# nuc5v2.net
KiCad netlist of a schematic drawn in Altium Designer
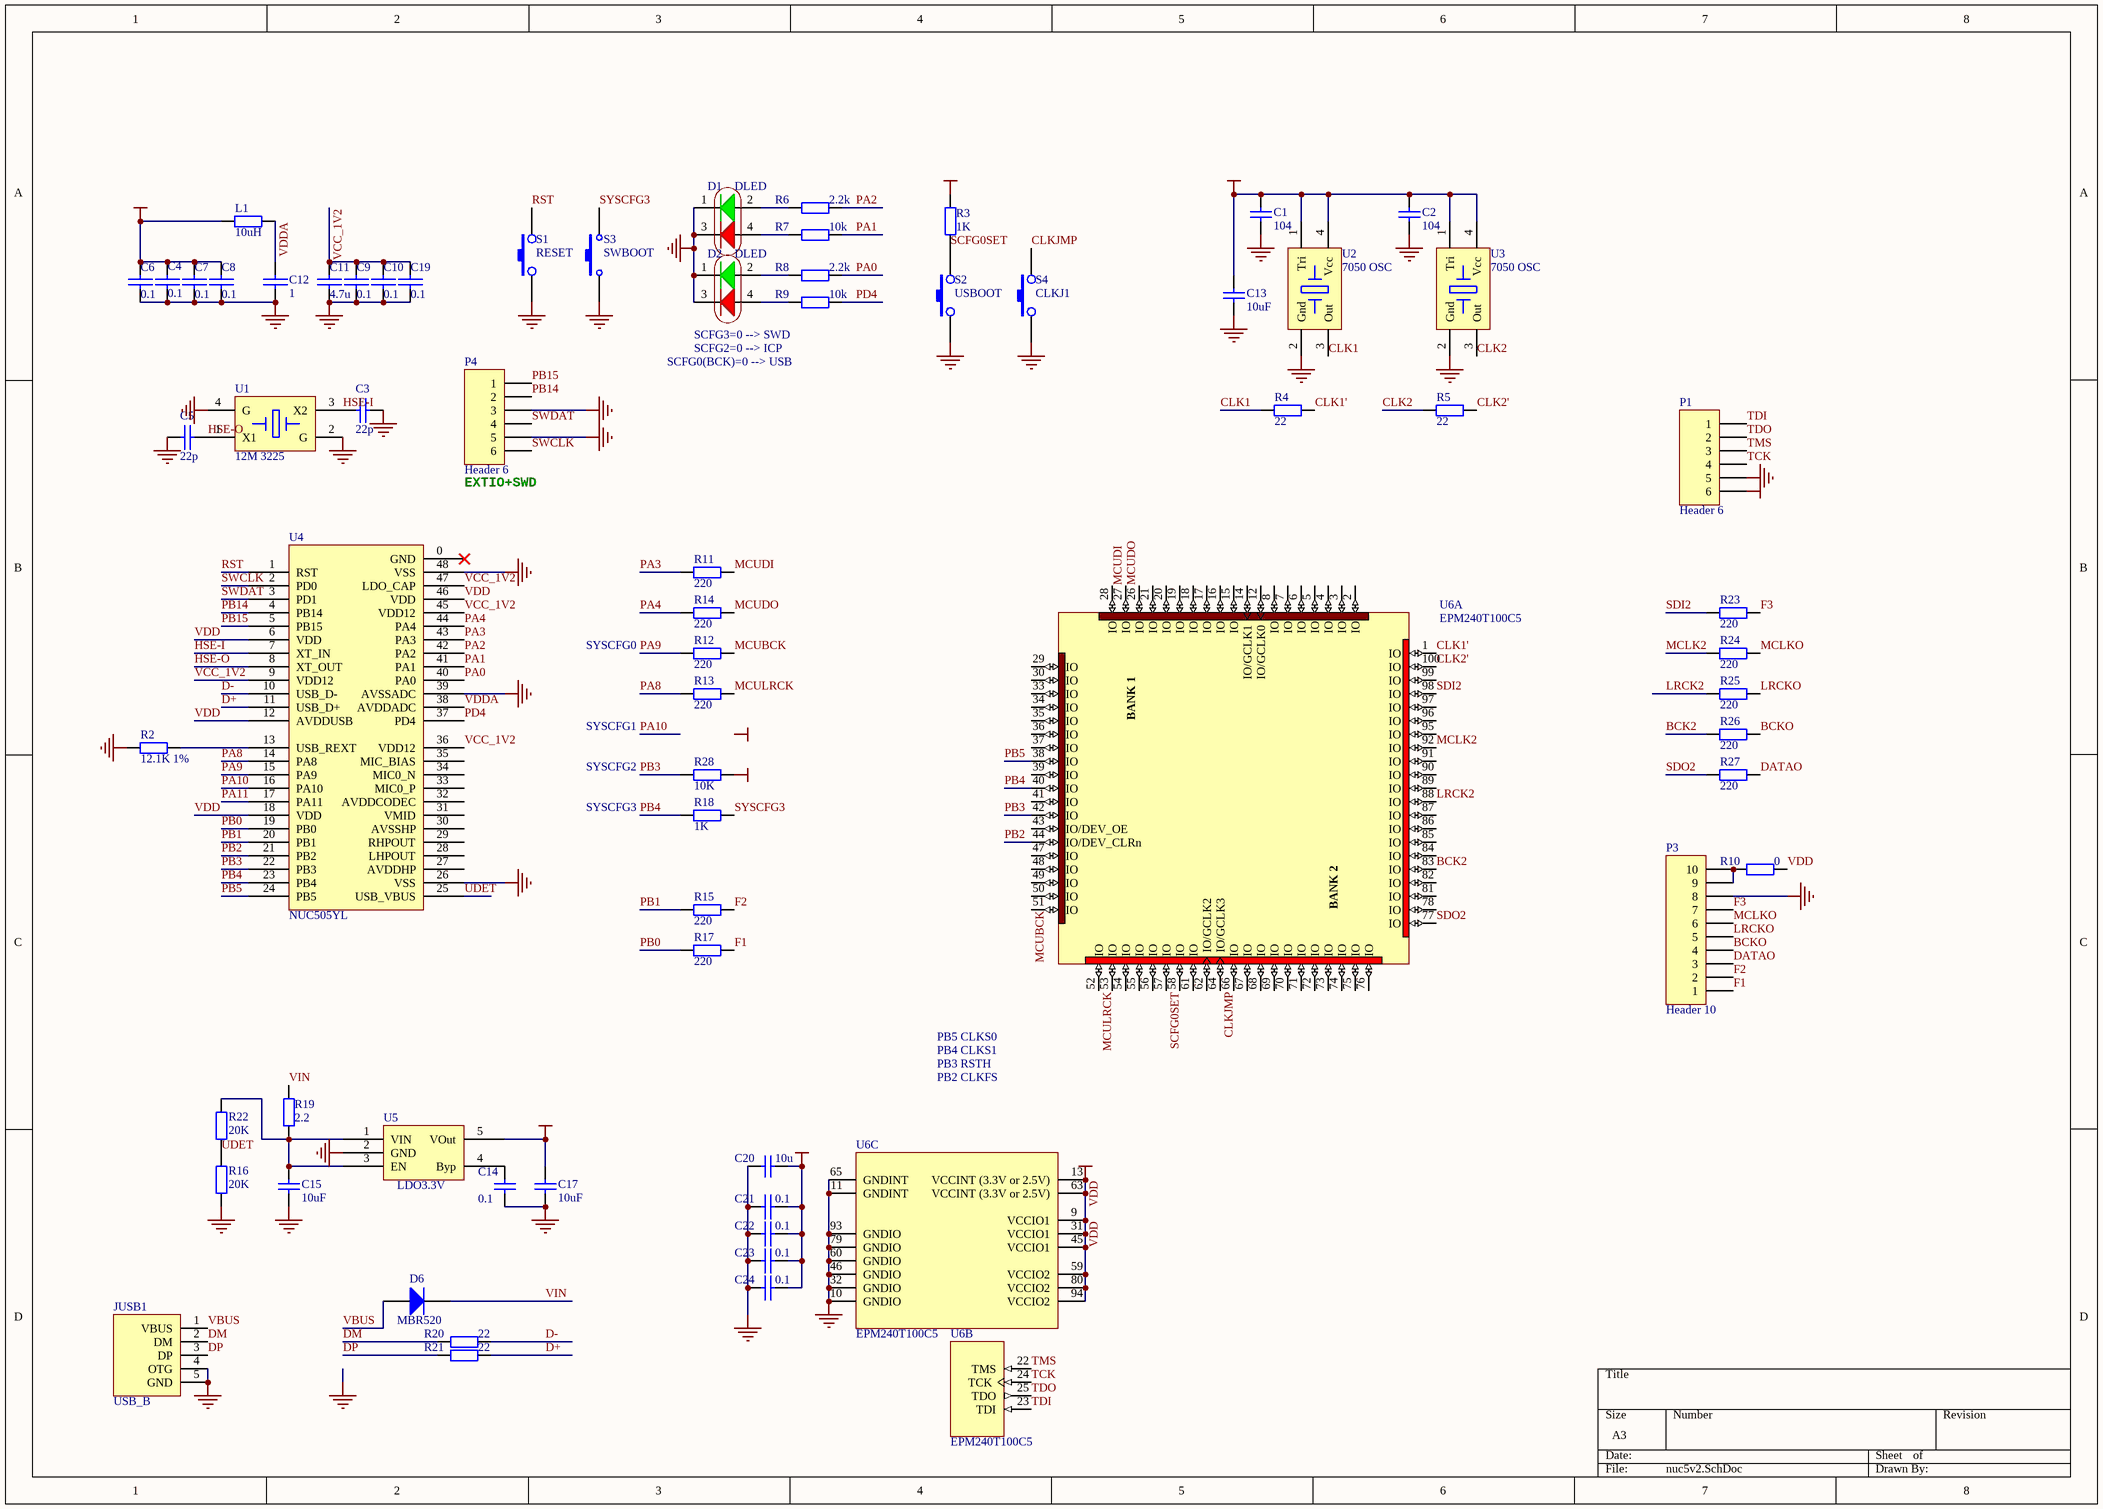
[diagram p0: nuc5v2.SchDoc]

(export (version "E")
  (design (tool "Eeschema 10.0.6"))
  (components
    (comp (ref "C1")
      (value "104")
      (footprint "0603")
      (description "Capacitor0603")
      (libsource (lib "ADI1955-Sch") (part "Cap6"))
    )
    (comp (ref "C2")
      (value "104")
      (footprint "0603")
      (description "Capacitor0603")
      (libsource (lib "ADI1955-Sch") (part "Cap6"))
    )
    (comp (ref "C3")
      (value "22p")
      (footprint "0603")
      (description "Capacitor")
      (libsource (lib "") (part "CAP_1"))
    )
    (comp (ref "C4")
      (value "0.1")
      (footprint "0603")
      (description "Capacitor")
      (libsource (lib "") (part "CAP_1"))
    )
    (comp (ref "C5")
      (value "22p")
      (footprint "0603")
      (description "Capacitor")
      (libsource (lib "*") (part "CAP"))
    )
    (comp (ref "C6")
      (value "0.1")
      (footprint "0603")
      (description "Capacitor")
      (libsource (lib "") (part "CAP_1"))
    )
    (comp (ref "C7")
      (value "0.1")
      (footprint "0603")
      (description "Capacitor")
      (libsource (lib "") (part "CAP_1"))
    )
    (comp (ref "C8")
      (value "0.1")
      (footprint "0603")
      (description "Capacitor")
      (libsource (lib "") (part "CAP_1"))
    )
    (comp (ref "C9")
      (value "0.1")
      (footprint "0603")
      (description "Capacitor")
      (libsource (lib "") (part "CAP_1"))
    )
    (comp (ref "C10")
      (value "0.1")
      (footprint "0603")
      (description "Capacitor")
      (libsource (lib "") (part "CAP_1"))
    )
    (comp (ref "C11")
      (value "4.7u")
      (footprint "0603")
      (description "Capacitor")
      (libsource (lib "") (part "CAP_1"))
    )
    (comp (ref "C12")
      (value "1")
      (footprint "0603")
      (description "Capacitor")
      (libsource (lib "") (part "CAP_1"))
    )
    (comp (ref "C13")
      (value "10uF")
      (footprint "CC0805CAP")
      (description "Capacitor0805")
      (libsource (lib "AudioLCR") (part "Cap8"))
    )
    (comp (ref "C14")
      (value "0.1")
      (footprint "0603")
      (description "Capacitor0805")
      (libsource (lib "*") (part "Cap8"))
    )
    (comp (ref "C15")
      (value "10uF")
      (footprint "CC0805CAP")
      (description "Capacitor0805")
      (libsource (lib "AudioLCR") (part "Cap8"))
    )
    (comp (ref "C17")
      (value "10uF")
      (footprint "CC0805CAP")
      (description "Capacitor0805")
      (libsource (lib "AudioLCR") (part "Cap8"))
    )
    (comp (ref "C19")
      (value "0.1")
      (footprint "0603")
      (description "Capacitor")
      (libsource (lib "") (part "CAP_1"))
    )
    (comp (ref "C20")
      (value "10u")
      (footprint "CC0805CAP")
      (description "Capacitor0805")
      (libsource (lib "S1-LCR") (part "Cap8"))
    )
    (comp (ref "C21")
      (value "0.1")
      (footprint "0603")
      (description "Capacitor")
      (libsource (lib "") (part "CAP_1"))
    )
    (comp (ref "C22")
      (value "0.1")
      (footprint "0603")
      (description "Capacitor")
      (libsource (lib "") (part "CAP_1"))
    )
    (comp (ref "C23")
      (value "0.1")
      (footprint "0603")
      (description "Capacitor")
      (libsource (lib "") (part "CAP_1"))
    )
    (comp (ref "C24")
      (value "0.1")
      (footprint "0603")
      (description "Capacitor")
      (libsource (lib "") (part "CAP_1"))
    )
    (comp (ref "D1")
      (value "DLED")
      (footprint "LED1204")
      (description "1204双色LED")
      (libsource (lib "S1-常用") (part "LED1204"))
    )
    (comp (ref "D2")
      (value "DLED")
      (footprint "LED1204")
      (description "1204双色LED")
      (libsource (lib "S1-常用") (part "LED1204"))
    )
    (comp (ref "D6")
      (value "MBR520")
      (footprint "SOD123")
      (description "Default Diode")
      (libsource (lib "Miscellaneous Devices") (part "Diode"))
    )
    (comp (ref "JUSB1")
      (value "USB_B")
      (footprint "USB-B-M")
      (description "USB Mini/Micro 5P")
      (libsource (lib "AudioLCR") (part "USB_B"))
    )
    (comp (ref "L1")
      (value "10uH")
      (footprint "CC0805RES")
      (description "Resistor0805")
      (libsource (lib "ADI1955-Sch") (part "Res8"))
    )
    (comp (ref "P1")
      (value "Header 6")
      (footprint "密脚针1.27mm*6")
      (description "Header, 6-Pin")
      (fields (field (name "PUBLISHER") "Altium Limited"))
      (libsource (lib "Miscellaneous Connectors") (part "Header 6"))
    )
    (comp (ref "P3")
      (value "Header 10")
      (footprint "HDR1X10")
      (description "Header, 10-Pin")
      (fields (field (name "PUBLISHER") "Altium Limited"))
      (libsource (lib "Miscellaneous Connectors") (part "Header 10"))
    )
    (comp (ref "P4")
      (value "Header 6")
      (footprint "密脚针1.27mm*6")
      (description "Header, 6-Pin")
      (fields (field (name "PUBLISHER") "Altium Limited"))
      (libsource (lib "Miscellaneous Connectors") (part "Header 6"))
    )
    (comp (ref "R2")
      (value "12.1K 1%")
      (footprint "CR1005-0402")
      (description "Resistor0603")
      (libsource (lib "S1-LCR") (part "Res6"))
    )
    (comp (ref "R3")
      (value "1K")
      (footprint "CR1005-0402")
      (description "Resistor0603")
      (libsource (lib "") (part "Res6_1"))
    )
    (comp (ref "R4")
      (value "22")
      (footprint "CR1005-0402")
      (description "Resistor0603")
      (libsource (lib "*") (part "Res6"))
    )
    (comp (ref "R5")
      (value "22")
      (footprint "CR1005-0402")
      (description "Resistor0603")
      (libsource (lib "*") (part "Res6"))
    )
    (comp (ref "R6")
      (value "2.2k")
      (footprint "CR1005-0402")
      (description "Resistor0603")
      (libsource (lib "ADI1955-Sch") (part "Res6"))
    )
    (comp (ref "R7")
      (value "10k")
      (footprint "CR1005-0402")
      (description "Resistor0603")
      (libsource (lib "ADI1955-Sch") (part "Res6"))
    )
    (comp (ref "R8")
      (value "2.2k")
      (footprint "CR1005-0402")
      (description "Resistor0603")
      (libsource (lib "ADI1955-Sch") (part "Res6"))
    )
    (comp (ref "R9")
      (value "10k")
      (footprint "CR1005-0402")
      (description "Resistor0603")
      (libsource (lib "ADI1955-Sch") (part "Res6"))
    )
    (comp (ref "R10")
      (value "0")
      (footprint "0603")
      (description "Resistor0603")
      (libsource (lib "ADI1955-Sch") (part "Res6"))
    )
    (comp (ref "R11")
      (value "220")
      (footprint "CR1005-0402")
      (description "Resistor0603")
      (libsource (lib "*") (part "Res6"))
    )
    (comp (ref "R12")
      (value "220")
      (footprint "CR1005-0402")
      (description "Resistor0603")
      (libsource (lib "") (part "Res6_2"))
    )
    (comp (ref "R13")
      (value "220")
      (footprint "CR1005-0402")
      (description "Resistor0603")
      (libsource (lib "*") (part "Res6"))
    )
    (comp (ref "R14")
      (value "220")
      (footprint "CR1005-0402")
      (description "Resistor0603")
      (libsource (lib "ADI1955-Sch") (part "Res6"))
    )
    (comp (ref "R15")
      (value "220")
      (footprint "CR1005-0402")
      (description "Resistor0603")
      (libsource (lib "ADI1955-Sch") (part "Res6"))
    )
    (comp (ref "R16")
      (value "20K")
      (footprint "CR1005-0402")
      (description "贴片电阻")
      (libsource (lib "MY LIB") (part "R"))
    )
    (comp (ref "R17")
      (value "220")
      (footprint "CR1005-0402")
      (description "Resistor0603")
      (libsource (lib "ADI1955-Sch") (part "Res6"))
    )
    (comp (ref "R18")
      (value "1K")
      (footprint "CR1005-0402")
      (description "Resistor0603")
      (libsource (lib "*") (part "Res6"))
    )
    (comp (ref "R19")
      (value "2.2")
      (footprint "CC0603RES")
      (description "Resistor0603")
      (libsource (lib "AudioLCR") (part "Res6"))
    )
    (comp (ref "R20")
      (value "22")
      (footprint "CR1005-0402")
      (description "Resistor0603")
      (libsource (lib "ADI1955-Sch") (part "Res6"))
    )
    (comp (ref "R21")
      (value "22")
      (footprint "CR1005-0402")
      (description "Resistor0603")
      (libsource (lib "ADI1955-Sch") (part "Res6"))
    )
    (comp (ref "R22")
      (value "20K")
      (footprint "CR1005-0402")
      (description "贴片电阻")
      (libsource (lib "MY LIB") (part "R"))
    )
    (comp (ref "R23")
      (value "220")
      (footprint "CR1005-0402")
      (description "Resistor0603")
      (libsource (lib "*") (part "Res6"))
    )
    (comp (ref "R24")
      (value "220")
      (footprint "CR1005-0402")
      (description "Resistor0603")
      (libsource (lib "ADI1955-Sch") (part "Res6"))
    )
    (comp (ref "R25")
      (value "220")
      (footprint "CR1005-0402")
      (description "Resistor0603")
      (libsource (lib "") (part "Res6_2"))
    )
    (comp (ref "R26")
      (value "220")
      (footprint "CR1005-0402")
      (description "Resistor0603")
      (libsource (lib "*") (part "Res6"))
    )
    (comp (ref "R27")
      (value "220")
      (footprint "CR1005-0402")
      (description "Resistor0603")
      (libsource (lib "*") (part "Res6"))
    )
    (comp (ref "R28")
      (value "10K")
      (footprint "CR1005-0402")
      (description "Resistor0603")
      (libsource (lib "*") (part "Res6"))
    )
    (comp (ref "S1") (value "RESET") (footprint "密脚针1.27mm*2") (libsource (lib "*") (part "SW-PB")))
    (comp (ref "S2") (value "USBOOT") (footprint "密脚针1.27mm*2") (libsource (lib "*") (part "SW-PB")))
    (comp (ref "S3")
      (value "SWBOOT")
      (footprint "密脚针1.27mm*2")
      (description "Switch")
      (fields (field (name "PUBLISHER") "Altium Limited"))
      (libsource (lib "Miscellaneous Devices") (part "SW-PB"))
    )
    (comp (ref "S4") (value "CLKJ1") (footprint "密脚针1.27mm*2") (libsource (lib "*") (part "SW-PB")))
    (comp (ref "U1") (value "12M 3225") (footprint "OSC-3225") (libsource (lib "AudioLCR") (part "XTAL")))
    (comp (ref "U2") (value "7050 OSC") (footprint "OSC-3225") (libsource (lib "AudioLCR") (part "XTAL_OSC")))
    (comp (ref "U3") (value "7050 OSC") (footprint "OSC-3225") (libsource (lib "AudioLCR") (part "XTAL_OSC")))
    (comp (ref "U4") (value "NUC505YL") (footprint "LQFP-48") (libsource (lib "NUC505YL") (part "NUC505YL")))
    (comp (ref "U5")
      (value "LDO3.3V")
      (footprint "SOT23-5")
      (description "LP2985 5V LDO")
      (libsource (lib "ADI1955-Sch") (part "LP2985-5"))
    )
    (comp (ref "U6")
      (value "EPM240T100C5")
      (footprint "TQFP100")
      (description "MAX II 2.5/3.3V CPLD, 80 I/Os, 100-Pin Plastic TQFP, Commercial Temperature, Speed Grade 5")
      (fields (field (name "PUBLISHER") "Altium Limited"))
      (libsource (lib "Altera MAX II") (part "EPM240T100C5"))
    )
  )
  (nets
    (net (code "1") (name "/BCK2") (class "Default")
      (node (ref "R26") (pin "1") (pinfunction "1_1") (pintype "passive"))
      (node (ref "U6") (pin "83") (pinfunction "IO_83") (pintype "bidirectional"))
    )
    (net (code "2") (name "/BCKO") (class "Default")
      (node (ref "P3") (pin "4") (pinfunction "4_4") (pintype "passive"))
      (node (ref "R26") (pin "2") (pinfunction "2_2") (pintype "passive"))
    )
    (net (code "3") (name "/CLK1") (class "Default")
      (node (ref "R4") (pin "1") (pinfunction "1_1") (pintype "passive"))
      (node (ref "U2") (pin "3") (pinfunction "Out_3") (pintype "passive"))
    )
    (net (code "4") (name "/CLK1'") (class "Default")
      (node (ref "R4") (pin "2") (pinfunction "2_2") (pintype "passive"))
      (node (ref "U6") (pin "1") (pinfunction "IO_1") (pintype "bidirectional"))
    )
    (net (code "5") (name "/CLK2") (class "Default")
      (node (ref "R5") (pin "1") (pinfunction "1_1") (pintype "passive"))
      (node (ref "U3") (pin "3") (pinfunction "Out_3") (pintype "passive"))
    )
    (net (code "6") (name "/CLK2'") (class "Default")
      (node (ref "R5") (pin "2") (pinfunction "2_2") (pintype "passive"))
      (node (ref "U6") (pin "100") (pinfunction "IO_100") (pintype "bidirectional"))
    )
    (net (code "7") (name "/CLKJMP") (class "Default")
      (node (ref "S4") (pin "2") (pinfunction "2_2") (pintype "passive"))
      (node (ref "U6") (pin "64") (pinfunction "IO/GCLK3_64") (pintype "bidirectional"))
    )
    (net (code "8") (name "/D+") (class "Default")
      (node (ref "R21") (pin "1") (pinfunction "1_1") (pintype "passive"))
      (node (ref "U4") (pin "11") (pinfunction "USB_D+_11") (pintype "passive"))
    )
    (net (code "9") (name "/D-") (class "Default")
      (node (ref "R20") (pin "1") (pinfunction "1_1") (pintype "passive"))
      (node (ref "U4") (pin "10") (pinfunction "USB_D-_10") (pintype "passive"))
    )
    (net (code "10") (name "/DATAO") (class "Default")
      (node (ref "P3") (pin "3") (pinfunction "3_3") (pintype "passive"))
      (node (ref "R27") (pin "2") (pinfunction "2_2") (pintype "passive"))
    )
    (net (code "11") (name "/DM") (class "Default")
      (node (ref "JUSB1") (pin "2") (pinfunction "DM_2") (pintype "passive"))
      (node (ref "R20") (pin "2") (pinfunction "2_2") (pintype "passive"))
    )
    (net (code "12") (name "/DP") (class "Default")
      (node (ref "JUSB1") (pin "3") (pinfunction "DP_3") (pintype "passive"))
      (node (ref "R21") (pin "2") (pinfunction "2_2") (pintype "passive"))
    )
    (net (code "13") (name "/F1") (class "Default")
      (node (ref "P3") (pin "1") (pinfunction "1_1") (pintype "passive"))
      (node (ref "R17") (pin "1") (pinfunction "1_1") (pintype "passive"))
    )
    (net (code "14") (name "/F2") (class "Default")
      (node (ref "P3") (pin "2") (pinfunction "2_2") (pintype "passive"))
      (node (ref "R15") (pin "1") (pinfunction "1_1") (pintype "passive"))
    )
    (net (code "15") (name "/F3") (class "Default")
      (node (ref "P3") (pin "7") (pinfunction "7_7") (pintype "passive"))
      (node (ref "R23") (pin "2") (pinfunction "2_2") (pintype "passive"))
    )
    (net (code "16") (name "/HSE-I") (class "Default")
      (node (ref "C3") (pin "1") (pinfunction "1_1") (pintype "passive"))
      (node (ref "U1") (pin "3") (pinfunction "X2_3") (pintype "passive"))
      (node (ref "U4") (pin "7") (pinfunction "XT_IN_7") (pintype "passive"))
    )
    (net (code "17") (name "/HSE-O") (class "Default")
      (node (ref "C5") (pin "2") (pinfunction "2_2") (pintype "passive"))
      (node (ref "U1") (pin "1") (pinfunction "X1_1") (pintype "passive"))
      (node (ref "U4") (pin "8") (pinfunction "XT_OUT_8") (pintype "passive"))
    )
    (net (code "18") (name "/LRCK2") (class "Default")
      (node (ref "R25") (pin "2") (pinfunction "2_2") (pintype "passive"))
      (node (ref "U6") (pin "88") (pinfunction "IO_88") (pintype "bidirectional"))
    )
    (net (code "19") (name "/LRCKO") (class "Default")
      (node (ref "P3") (pin "5") (pinfunction "5_5") (pintype "passive"))
      (node (ref "R25") (pin "1") (pinfunction "1_1") (pintype "passive"))
    )
    (net (code "20") (name "/MCLK2") (class "Default")
      (node (ref "R24") (pin "2") (pinfunction "2_2") (pintype "passive"))
      (node (ref "U6") (pin "92") (pinfunction "IO_92") (pintype "bidirectional"))
    )
    (net (code "21") (name "/MCLKO") (class "Default")
      (node (ref "P3") (pin "6") (pinfunction "6_6") (pintype "passive"))
      (node (ref "R24") (pin "1") (pinfunction "1_1") (pintype "passive"))
    )
    (net (code "22") (name "/MCUBCK") (class "Default")
      (node (ref "R12") (pin "1") (pinfunction "1_1") (pintype "passive"))
      (node (ref "U6") (pin "51") (pinfunction "IO_51") (pintype "bidirectional"))
    )
    (net (code "23") (name "/MCUDI") (class "Default")
      (node (ref "R11") (pin "2") (pinfunction "2_2") (pintype "passive"))
      (node (ref "U6") (pin "27") (pinfunction "IO_27") (pintype "bidirectional"))
    )
    (net (code "24") (name "/MCUDO") (class "Default")
      (node (ref "R14") (pin "1") (pinfunction "1_1") (pintype "passive"))
      (node (ref "U6") (pin "26") (pinfunction "IO_26") (pintype "bidirectional"))
    )
    (net (code "25") (name "/MCULRCK") (class "Default")
      (node (ref "R13") (pin "2") (pinfunction "2_2") (pintype "passive"))
      (node (ref "U6") (pin "52") (pinfunction "IO_52") (pintype "bidirectional"))
    )
    (net (code "26") (name "/PA0") (class "Default")
      (node (ref "R8") (pin "1") (pinfunction "1_1") (pintype "passive"))
      (node (ref "U4") (pin "40") (pinfunction "PA0_40") (pintype "passive"))
    )
    (net (code "27") (name "/PA1") (class "Default")
      (node (ref "R7") (pin "1") (pinfunction "1_1") (pintype "passive"))
      (node (ref "U4") (pin "41") (pinfunction "PA1_41") (pintype "passive"))
    )
    (net (code "28") (name "/PA2") (class "Default")
      (node (ref "R6") (pin "1") (pinfunction "1_1") (pintype "passive"))
      (node (ref "U4") (pin "42") (pinfunction "PA2_42") (pintype "passive"))
    )
    (net (code "29") (name "/PA3") (class "Default")
      (node (ref "R11") (pin "1") (pinfunction "1_1") (pintype "passive"))
      (node (ref "U4") (pin "43") (pinfunction "PA3_43") (pintype "passive"))
    )
    (net (code "30") (name "/PA4") (class "Default")
      (node (ref "R14") (pin "2") (pinfunction "2_2") (pintype "passive"))
      (node (ref "U4") (pin "44") (pinfunction "PA4_44") (pintype "passive"))
    )
    (net (code "31") (name "/PA8") (class "Default")
      (node (ref "R13") (pin "1") (pinfunction "1_1") (pintype "passive"))
      (node (ref "U4") (pin "14") (pinfunction "PA8_14") (pintype "passive"))
    )
    (net (code "32") (name "/PA9") (class "Default")
      (node (ref "R12") (pin "2") (pinfunction "2_2") (pintype "passive"))
      (node (ref "U4") (pin "15") (pinfunction "PA9_15") (pintype "passive"))
    )
    (net (code "33") (name "/PA10") (class "Default")
      (node (ref "U4") (pin "16") (pinfunction "PA10_16") (pintype "passive"))
    )
    (net (code "34") (name "/PA11") (class "Default")
      (node (ref "U4") (pin "17") (pinfunction "PA11_17") (pintype "passive"))
    )
    (net (code "35") (name "/PB0") (class "Default")
      (node (ref "R17") (pin "2") (pinfunction "2_2") (pintype "passive"))
      (node (ref "U4") (pin "19") (pinfunction "PB0_19") (pintype "passive"))
    )
    (net (code "36") (name "/PB1") (class "Default")
      (node (ref "R15") (pin "2") (pinfunction "2_2") (pintype "passive"))
      (node (ref "U4") (pin "20") (pinfunction "PB1_20") (pintype "passive"))
    )
    (net (code "37") (name "/PB2") (class "Default")
      (node (ref "U4") (pin "21") (pinfunction "PB2_21") (pintype "passive"))
      (node (ref "U6") (pin "44") (pinfunction "IO/DEV_CLRn_44") (pintype "bidirectional"))
    )
    (net (code "38") (name "/PB3") (class "Default")
      (node (ref "R28") (pin "1") (pinfunction "1_1") (pintype "passive"))
      (node (ref "U4") (pin "22") (pinfunction "PB3_22") (pintype "passive"))
      (node (ref "U6") (pin "42") (pinfunction "IO_42") (pintype "bidirectional"))
    )
    (net (code "39") (name "/PB4") (class "Default")
      (node (ref "R18") (pin "1") (pinfunction "1_1") (pintype "passive"))
      (node (ref "U4") (pin "23") (pinfunction "PB4_23") (pintype "passive"))
      (node (ref "U6") (pin "40") (pinfunction "IO_40") (pintype "bidirectional"))
    )
    (net (code "40") (name "/PB5") (class "Default")
      (node (ref "U4") (pin "24") (pinfunction "PB5_24") (pintype "passive"))
      (node (ref "U6") (pin "38") (pinfunction "IO_38") (pintype "bidirectional"))
    )
    (net (code "41") (name "/PB14") (class "Default")
      (node (ref "P4") (pin "2") (pinfunction "2_2") (pintype "passive"))
      (node (ref "U4") (pin "4") (pinfunction "PB14_4") (pintype "passive"))
    )
    (net (code "42") (name "/PB15") (class "Default")
      (node (ref "P4") (pin "1") (pinfunction "1_1") (pintype "passive"))
      (node (ref "U4") (pin "5") (pinfunction "PB15_5") (pintype "passive"))
    )
    (net (code "43") (name "/PD4") (class "Default")
      (node (ref "R9") (pin "1") (pinfunction "1_1") (pintype "passive"))
      (node (ref "U4") (pin "37") (pinfunction "PD4_37") (pintype "passive"))
    )
    (net (code "44") (name "/RST") (class "Default")
      (node (ref "S1") (pin "2") (pinfunction "2_2") (pintype "passive"))
      (node (ref "U4") (pin "1") (pinfunction "RST_1") (pintype "passive"))
    )
    (net (code "45") (name "/SCFG0SET") (class "Default")
      (node (ref "R3") (pin "1") (pinfunction "1_1") (pintype "passive"))
      (node (ref "S2") (pin "2") (pinfunction "2_2") (pintype "passive"))
      (node (ref "U6") (pin "57") (pinfunction "IO_57") (pintype "bidirectional"))
    )
    (net (code "46") (name "/SDI2") (class "Default")
      (node (ref "R23") (pin "1") (pinfunction "1_1") (pintype "passive"))
      (node (ref "U6") (pin "98") (pinfunction "IO_98") (pintype "bidirectional"))
    )
    (net (code "47") (name "/SDO2") (class "Default")
      (node (ref "R27") (pin "1") (pinfunction "1_1") (pintype "passive"))
      (node (ref "U6") (pin "77") (pinfunction "IO_77") (pintype "bidirectional"))
    )
    (net (code "48") (name "/SWCLK") (class "Default")
      (node (ref "P4") (pin "6") (pinfunction "6_6") (pintype "passive"))
      (node (ref "U4") (pin "2") (pinfunction "PD0_2") (pintype "passive"))
    )
    (net (code "49") (name "/SWDAT") (class "Default")
      (node (ref "P4") (pin "4") (pinfunction "4_4") (pintype "passive"))
      (node (ref "U4") (pin "3") (pinfunction "PD1_3") (pintype "passive"))
    )
    (net (code "50") (name "/SYSCFG3") (class "Default")
      (node (ref "R18") (pin "2") (pinfunction "2_2") (pintype "passive"))
      (node (ref "S3") (pin "2") (pinfunction "2_2") (pintype "passive"))
    )
    (net (code "51") (name "/TCK") (class "Default")
      (node (ref "P1") (pin "4") (pinfunction "4_4") (pintype "passive"))
      (node (ref "U6") (pin "24") (pinfunction "TCK_24") (pintype "input"))
    )
    (net (code "52") (name "/TDI") (class "Default")
      (node (ref "P1") (pin "1") (pinfunction "1_1") (pintype "passive"))
      (node (ref "U6") (pin "23") (pinfunction "TDI_23") (pintype "input"))
    )
    (net (code "53") (name "/TDO") (class "Default")
      (node (ref "P1") (pin "2") (pinfunction "2_2") (pintype "passive"))
      (node (ref "U6") (pin "25") (pinfunction "TDO_25") (pintype "output"))
    )
    (net (code "54") (name "/TMS") (class "Default")
      (node (ref "P1") (pin "3") (pinfunction "3_3") (pintype "passive"))
      (node (ref "U6") (pin "22") (pinfunction "TMS_22") (pintype "input"))
    )
    (net (code "55") (name "/UDET") (class "Default")
      (node (ref "R16") (pin "2") (pinfunction "2_2") (pintype "passive"))
      (node (ref "R22") (pin "1") (pinfunction "1_1") (pintype "passive"))
      (node (ref "U4") (pin "25") (pinfunction "USB_VBUS_25") (pintype "passive"))
    )
    (net (code "56") (name "/VBUS") (class "Default")
      (node (ref "D6") (pin "1") (pinfunction "A_1") (pintype "passive"))
      (node (ref "JUSB1") (pin "1") (pinfunction "VBUS_1") (pintype "passive"))
    )
    (net (code "57") (name "/VCC_1V2") (class "Default")
      (node (ref "C10") (pin "1") (pinfunction "1_1") (pintype "passive"))
      (node (ref "C11") (pin "1") (pinfunction "1_1") (pintype "passive"))
      (node (ref "C19") (pin "1") (pinfunction "1_1") (pintype "passive"))
      (node (ref "C9") (pin "1") (pinfunction "1_1") (pintype "passive"))
      (node (ref "U4") (pin "36") (pinfunction "VDD12_36") (pintype "passive"))
      (node (ref "U4") (pin "45") (pinfunction "VDD12_45") (pintype "passive"))
      (node (ref "U4") (pin "47") (pinfunction "LDO_CAP_47") (pintype "passive"))
      (node (ref "U4") (pin "9") (pinfunction "VDD12_9") (pintype "passive"))
    )
    (net (code "58") (name "/VDDA") (class "Default")
      (node (ref "C12") (pin "1") (pinfunction "1_1") (pintype "passive"))
      (node (ref "L1") (pin "2") (pinfunction "2_2") (pintype "passive"))
      (node (ref "U4") (pin "38") (pinfunction "AVDDADC_38") (pintype "passive"))
    )
    (net (code "59") (name "/VIN") (class "Default")
      (node (ref "D6") (pin "2") (pinfunction "K_2") (pintype "passive"))
      (node (ref "R19") (pin "1") (pinfunction "1_1") (pintype "passive"))
    )
    (net (code "60") (name "GND") (class "Default")
      (node (ref "C1") (pin "1") (pinfunction "1_1") (pintype "passive"))
      (node (ref "C10") (pin "2") (pinfunction "2_2") (pintype "passive"))
      (node (ref "C11") (pin "2") (pinfunction "2_2") (pintype "passive"))
      (node (ref "C12") (pin "2") (pinfunction "2_2") (pintype "passive"))
      (node (ref "C13") (pin "1") (pinfunction "1_1") (pintype "passive"))
      (node (ref "C14") (pin "2") (pinfunction "2_2") (pintype "passive"))
      (node (ref "C15") (pin "1") (pinfunction "1_1") (pintype "passive"))
      (node (ref "C17") (pin "1") (pinfunction "1_1") (pintype "passive"))
      (node (ref "C19") (pin "2") (pinfunction "2_2") (pintype "passive"))
      (node (ref "C2") (pin "2") (pinfunction "2_2") (pintype "passive"))
      (node (ref "C20") (pin "2") (pinfunction "2_2") (pintype "passive"))
      (node (ref "C21") (pin "1") (pinfunction "1_1") (pintype "passive"))
      (node (ref "C22") (pin "1") (pinfunction "1_1") (pintype "passive"))
      (node (ref "C23") (pin "1") (pinfunction "1_1") (pintype "passive"))
      (node (ref "C24") (pin "1") (pinfunction "1_1") (pintype "passive"))
      (node (ref "C3") (pin "2") (pinfunction "2_2") (pintype "passive"))
      (node (ref "C4") (pin "2") (pinfunction "2_2") (pintype "passive"))
      (node (ref "C5") (pin "1") (pinfunction "1_1") (pintype "passive"))
      (node (ref "C6") (pin "2") (pinfunction "2_2") (pintype "passive"))
      (node (ref "C7") (pin "1") (pinfunction "1_1") (pintype "passive"))
      (node (ref "C8") (pin "2") (pinfunction "2_2") (pintype "passive"))
      (node (ref "C9") (pin "2") (pinfunction "2_2") (pintype "passive"))
      (node (ref "D1") (pin "1") (pinfunction "1_1") (pintype "passive"))
      (node (ref "D1") (pin "3") (pinfunction "3_3") (pintype "passive"))
      (node (ref "D2") (pin "1") (pinfunction "1_1") (pintype "passive"))
      (node (ref "D2") (pin "3") (pinfunction "3_3") (pintype "passive"))
      (node (ref "JUSB1") (pin "4") (pinfunction "OTG_4") (pintype "passive"))
      (node (ref "JUSB1") (pin "5") (pinfunction "GND_5") (pintype "passive"))
      (node (ref "P1") (pin "5") (pinfunction "5_5") (pintype "passive"))
      (node (ref "P3") (pin "8") (pinfunction "8_8") (pintype "passive"))
      (node (ref "P4") (pin "3") (pinfunction "3_3") (pintype "passive"))
      (node (ref "P4") (pin "5") (pinfunction "5_5") (pintype "passive"))
      (node (ref "R16") (pin "1") (pinfunction "1_1") (pintype "passive"))
      (node (ref "R2") (pin "2") (pinfunction "2_2") (pintype "passive"))
      (node (ref "S1") (pin "1") (pinfunction "1_1") (pintype "passive"))
      (node (ref "S2") (pin "1") (pinfunction "1_1") (pintype "passive"))
      (node (ref "S3") (pin "1") (pinfunction "1_1") (pintype "passive"))
      (node (ref "S4") (pin "1") (pinfunction "1_1") (pintype "passive"))
      (node (ref "U1") (pin "2") (pinfunction "G_2") (pintype "passive"))
      (node (ref "U1") (pin "4") (pinfunction "G_4") (pintype "passive"))
      (node (ref "U2") (pin "2") (pinfunction "Gnd_2") (pintype "passive"))
      (node (ref "U3") (pin "2") (pinfunction "Gnd_2") (pintype "passive"))
      (node (ref "U4") (pin "26") (pinfunction "VSS_26") (pintype "passive"))
      (node (ref "U4") (pin "39") (pinfunction "AVSSADC_39") (pintype "passive"))
      (node (ref "U4") (pin "48") (pinfunction "VSS_48") (pintype "passive"))
      (node (ref "U5") (pin "2") (pinfunction "GND_2") (pintype "passive"))
      (node (ref "U6") (pin "10") (pinfunction "GNDIO_10") (pintype "power_in"))
      (node (ref "U6") (pin "11") (pinfunction "GNDINT_11") (pintype "power_in"))
      (node (ref "U6") (pin "32") (pinfunction "GNDIO_32") (pintype "power_in"))
      (node (ref "U6") (pin "46") (pinfunction "GNDIO_46") (pintype "power_in"))
      (node (ref "U6") (pin "60") (pinfunction "GNDIO_60") (pintype "power_in"))
      (node (ref "U6") (pin "65") (pinfunction "GNDINT_65") (pintype "power_in"))
      (node (ref "U6") (pin "79") (pinfunction "GNDIO_79") (pintype "power_in"))
      (node (ref "U6") (pin "93") (pinfunction "GNDIO_93") (pintype "power_in"))
    )
    (net (code "61") (name "Net-(D1-Pad2)") (class "Default")
      (node (ref "D1") (pin "2") (pinfunction "2_2") (pintype "passive"))
      (node (ref "R6") (pin "2") (pinfunction "2_2") (pintype "passive"))
    )
    (net (code "62") (name "Net-(D1-Pad4)") (class "Default")
      (node (ref "D1") (pin "4") (pinfunction "4_4") (pintype "passive"))
      (node (ref "R7") (pin "2") (pinfunction "2_2") (pintype "passive"))
    )
    (net (code "63") (name "Net-(D2-Pad2)") (class "Default")
      (node (ref "D2") (pin "2") (pinfunction "2_2") (pintype "passive"))
      (node (ref "R8") (pin "2") (pinfunction "2_2") (pintype "passive"))
    )
    (net (code "64") (name "Net-(D2-Pad4)") (class "Default")
      (node (ref "D2") (pin "4") (pinfunction "4_4") (pintype "passive"))
      (node (ref "R9") (pin "2") (pinfunction "2_2") (pintype "passive"))
    )
    (net (code "65") (name "Net-(P3-Pad10)") (class "Default")
      (node (ref "P3") (pin "10") (pinfunction "10_10") (pintype "passive"))
      (node (ref "P3") (pin "9") (pinfunction "9_9") (pintype "passive"))
      (node (ref "R10") (pin "2") (pinfunction "2_2") (pintype "passive"))
    )
    (net (code "66") (name "Net-(U4-USB_REXT)") (class "Default")
      (node (ref "R2") (pin "1") (pinfunction "1_1") (pintype "passive"))
      (node (ref "U4") (pin "13") (pinfunction "USB_REXT_13") (pintype "passive"))
    )
    (net (code "67") (name "Net-(U5-Byp)") (class "Default")
      (node (ref "C14") (pin "1") (pinfunction "1_1") (pintype "passive"))
      (node (ref "U5") (pin "4") (pinfunction "Byp_4") (pintype "passive"))
    )
    (net (code "68") (name "Net-(U5-EN)") (class "Default")
      (node (ref "C15") (pin "2") (pinfunction "2_2") (pintype "passive"))
      (node (ref "R19") (pin "2") (pinfunction "2_2") (pintype "passive"))
      (node (ref "R22") (pin "2") (pinfunction "2_2") (pintype "passive"))
      (node (ref "U5") (pin "1") (pinfunction "VIN_1") (pintype "passive"))
      (node (ref "U5") (pin "3") (pinfunction "EN_3") (pintype "passive"))
    )
    (net (code "69") (name "VDD") (class "Default")
      (node (ref "C1") (pin "2") (pinfunction "2_2") (pintype "passive"))
      (node (ref "C13") (pin "2") (pinfunction "2_2") (pintype "passive"))
      (node (ref "C17") (pin "2") (pinfunction "2_2") (pintype "passive"))
      (node (ref "C2") (pin "1") (pinfunction "1_1") (pintype "passive"))
      (node (ref "C20") (pin "1") (pinfunction "1_1") (pintype "passive"))
      (node (ref "C21") (pin "2") (pinfunction "2_2") (pintype "passive"))
      (node (ref "C22") (pin "2") (pinfunction "2_2") (pintype "passive"))
      (node (ref "C23") (pin "2") (pinfunction "2_2") (pintype "passive"))
      (node (ref "C24") (pin "2") (pinfunction "2_2") (pintype "passive"))
      (node (ref "C4") (pin "1") (pinfunction "1_1") (pintype "passive"))
      (node (ref "C6") (pin "1") (pinfunction "1_1") (pintype "passive"))
      (node (ref "C7") (pin "2") (pinfunction "2_2") (pintype "passive"))
      (node (ref "C8") (pin "1") (pinfunction "1_1") (pintype "passive"))
      (node (ref "L1") (pin "1") (pinfunction "1_1") (pintype "passive"))
      (node (ref "P1") (pin "6") (pinfunction "6_6") (pintype "passive"))
      (node (ref "R10") (pin "1") (pinfunction "1_1") (pintype "passive"))
      (node (ref "R28") (pin "2") (pinfunction "2_2") (pintype "passive"))
      (node (ref "R3") (pin "2") (pinfunction "2_2") (pintype "passive"))
      (node (ref "U2") (pin "1") (pinfunction "Tri_1") (pintype "passive"))
      (node (ref "U2") (pin "4") (pinfunction "Vcc_4") (pintype "passive"))
      (node (ref "U3") (pin "1") (pinfunction "Tri_1") (pintype "passive"))
      (node (ref "U3") (pin "4") (pinfunction "Vcc_4") (pintype "passive"))
      (node (ref "U4") (pin "12") (pinfunction "AVDDUSB_12") (pintype "passive"))
      (node (ref "U4") (pin "18") (pinfunction "VDD_18") (pintype "passive"))
      (node (ref "U4") (pin "46") (pinfunction "VDD_46") (pintype "passive"))
      (node (ref "U4") (pin "6") (pinfunction "VDD_6") (pintype "passive"))
      (node (ref "U5") (pin "5") (pinfunction "VOut_5") (pintype "passive"))
      (node (ref "U6") (pin "13") (pinfunction "VCCINT_(3.3V_or_2.5V)_13") (pintype "power_in"))
      (node (ref "U6") (pin "31") (pinfunction "VCCIO1_31") (pintype "power_in"))
      (node (ref "U6") (pin "45") (pinfunction "VCCIO1_45") (pintype "power_in"))
      (node (ref "U6") (pin "59") (pinfunction "VCCIO2_59") (pintype "power_in"))
      (node (ref "U6") (pin "63") (pinfunction "VCCINT_(3.3V_or_2.5V)_63") (pintype "power_in"))
      (node (ref "U6") (pin "80") (pinfunction "VCCIO2_80") (pintype "power_in"))
      (node (ref "U6") (pin "9") (pinfunction "VCCIO1_9") (pintype "power_in"))
      (node (ref "U6") (pin "94") (pinfunction "VCCIO2_94") (pintype "power_in"))
    )
    (net (code "70") (name "unconnected-(U4-AVDDCODEC-Pad32)") (class "Default")
      (node (ref "U4") (pin "32") (pinfunction "AVDDCODEC_32") (pintype "passive"))
    )
    (net (code "71") (name "unconnected-(U4-AVDDHP-Pad27)") (class "Default")
      (node (ref "U4") (pin "27") (pinfunction "AVDDHP_27") (pintype "passive"))
    )
    (net (code "72") (name "unconnected-(U4-AVSSHP-Pad30)") (class "Default")
      (node (ref "U4") (pin "30") (pinfunction "AVSSHP_30") (pintype "passive"))
    )
    (net (code "73") (name "unconnected-(U4-GND-Pad0)") (class "Default")
      (node (ref "U4") (pin "0") (pinfunction "GND_0") (pintype "passive+no_connect"))
    )
    (net (code "74") (name "unconnected-(U4-LHPOUT-Pad28)") (class "Default")
      (node (ref "U4") (pin "28") (pinfunction "LHPOUT_28") (pintype "passive"))
    )
    (net (code "75") (name "unconnected-(U4-MIC0_N-Pad34)") (class "Default")
      (node (ref "U4") (pin "34") (pinfunction "MIC0_N_34") (pintype "passive"))
    )
    (net (code "76") (name "unconnected-(U4-MIC0_P-Pad33)") (class "Default")
      (node (ref "U4") (pin "33") (pinfunction "MIC0_P_33") (pintype "passive"))
    )
    (net (code "77") (name "unconnected-(U4-MIC_BIAS-Pad35)") (class "Default")
      (node (ref "U4") (pin "35") (pinfunction "MIC_BIAS_35") (pintype "passive"))
    )
    (net (code "78") (name "unconnected-(U4-RHPOUT-Pad29)") (class "Default")
      (node (ref "U4") (pin "29") (pinfunction "RHPOUT_29") (pintype "passive"))
    )
    (net (code "79") (name "unconnected-(U4-VMID-Pad31)") (class "Default")
      (node (ref "U4") (pin "31") (pinfunction "VMID_31") (pintype "passive"))
    )
    (net (code "80") (name "unconnected-(U6A-IO-Pad2)") (class "Default")
      (node (ref "U6") (pin "2") (pinfunction "IO_2") (pintype "bidirectional"))
    )
    (net (code "81") (name "unconnected-(U6A-IO-Pad3)") (class "Default")
      (node (ref "U6") (pin "3") (pinfunction "IO_3") (pintype "bidirectional"))
    )
    (net (code "82") (name "unconnected-(U6A-IO-Pad4)") (class "Default")
      (node (ref "U6") (pin "4") (pinfunction "IO_4") (pintype "bidirectional"))
    )
    (net (code "83") (name "unconnected-(U6A-IO-Pad5)") (class "Default")
      (node (ref "U6") (pin "5") (pinfunction "IO_5") (pintype "bidirectional"))
    )
    (net (code "84") (name "unconnected-(U6A-IO-Pad6)") (class "Default")
      (node (ref "U6") (pin "6") (pinfunction "IO_6") (pintype "bidirectional"))
    )
    (net (code "85") (name "unconnected-(U6A-IO-Pad7)") (class "Default")
      (node (ref "U6") (pin "7") (pinfunction "IO_7") (pintype "bidirectional"))
    )
    (net (code "86") (name "unconnected-(U6A-IO-Pad8)") (class "Default")
      (node (ref "U6") (pin "8") (pinfunction "IO_8") (pintype "bidirectional"))
    )
    (net (code "87") (name "unconnected-(U6A-IO-Pad15)") (class "Default")
      (node (ref "U6") (pin "15") (pinfunction "IO_15") (pintype "bidirectional"))
    )
    (net (code "88") (name "unconnected-(U6A-IO-Pad16)") (class "Default")
      (node (ref "U6") (pin "16") (pinfunction "IO_16") (pintype "bidirectional"))
    )
    (net (code "89") (name "unconnected-(U6A-IO-Pad17)") (class "Default")
      (node (ref "U6") (pin "17") (pinfunction "IO_17") (pintype "bidirectional"))
    )
    (net (code "90") (name "unconnected-(U6A-IO-Pad18)") (class "Default")
      (node (ref "U6") (pin "18") (pinfunction "IO_18") (pintype "bidirectional"))
    )
    (net (code "91") (name "unconnected-(U6A-IO-Pad19)") (class "Default")
      (node (ref "U6") (pin "19") (pinfunction "IO_19") (pintype "bidirectional"))
    )
    (net (code "92") (name "unconnected-(U6A-IO-Pad20)") (class "Default")
      (node (ref "U6") (pin "20") (pinfunction "IO_20") (pintype "bidirectional"))
    )
    (net (code "93") (name "unconnected-(U6A-IO-Pad21)") (class "Default")
      (node (ref "U6") (pin "21") (pinfunction "IO_21") (pintype "bidirectional"))
    )
    (net (code "94") (name "unconnected-(U6A-IO-Pad28)") (class "Default")
      (node (ref "U6") (pin "28") (pinfunction "IO_28") (pintype "bidirectional"))
    )
    (net (code "95") (name "unconnected-(U6A-IO-Pad29)") (class "Default")
      (node (ref "U6") (pin "29") (pinfunction "IO_29") (pintype "bidirectional"))
    )
    (net (code "96") (name "unconnected-(U6A-IO-Pad30)") (class "Default")
      (node (ref "U6") (pin "30") (pinfunction "IO_30") (pintype "bidirectional"))
    )
    (net (code "97") (name "unconnected-(U6A-IO-Pad33)") (class "Default")
      (node (ref "U6") (pin "33") (pinfunction "IO_33") (pintype "bidirectional"))
    )
    (net (code "98") (name "unconnected-(U6A-IO-Pad34)") (class "Default")
      (node (ref "U6") (pin "34") (pinfunction "IO_34") (pintype "bidirectional"))
    )
    (net (code "99") (name "unconnected-(U6A-IO-Pad35)") (class "Default")
      (node (ref "U6") (pin "35") (pinfunction "IO_35") (pintype "bidirectional"))
    )
    (net (code "100") (name "unconnected-(U6A-IO-Pad36)") (class "Default")
      (node (ref "U6") (pin "36") (pinfunction "IO_36") (pintype "bidirectional"))
    )
    (net (code "101") (name "unconnected-(U6A-IO-Pad37)") (class "Default")
      (node (ref "U6") (pin "37") (pinfunction "IO_37") (pintype "bidirectional"))
    )
    (net (code "102") (name "unconnected-(U6A-IO-Pad39)") (class "Default")
      (node (ref "U6") (pin "39") (pinfunction "IO_39") (pintype "bidirectional"))
    )
    (net (code "103") (name "unconnected-(U6A-IO-Pad41)") (class "Default")
      (node (ref "U6") (pin "41") (pinfunction "IO_41") (pintype "bidirectional"))
    )
    (net (code "104") (name "unconnected-(U6A-IO-Pad47)") (class "Default")
      (node (ref "U6") (pin "47") (pinfunction "IO_47") (pintype "bidirectional"))
    )
    (net (code "105") (name "unconnected-(U6A-IO-Pad48)") (class "Default")
      (node (ref "U6") (pin "48") (pinfunction "IO_48") (pintype "bidirectional"))
    )
    (net (code "106") (name "unconnected-(U6A-IO-Pad49)") (class "Default")
      (node (ref "U6") (pin "49") (pinfunction "IO_49") (pintype "bidirectional"))
    )
    (net (code "107") (name "unconnected-(U6A-IO-Pad50)") (class "Default")
      (node (ref "U6") (pin "50") (pinfunction "IO_50") (pintype "bidirectional"))
    )
    (net (code "108") (name "unconnected-(U6A-IO-Pad53)") (class "Default")
      (node (ref "U6") (pin "53") (pinfunction "IO_53") (pintype "bidirectional"))
    )
    (net (code "109") (name "unconnected-(U6A-IO-Pad54)") (class "Default")
      (node (ref "U6") (pin "54") (pinfunction "IO_54") (pintype "bidirectional"))
    )
    (net (code "110") (name "unconnected-(U6A-IO-Pad55)") (class "Default")
      (node (ref "U6") (pin "55") (pinfunction "IO_55") (pintype "bidirectional"))
    )
    (net (code "111") (name "unconnected-(U6A-IO-Pad56)") (class "Default")
      (node (ref "U6") (pin "56") (pinfunction "IO_56") (pintype "bidirectional"))
    )
    (net (code "112") (name "unconnected-(U6A-IO-Pad58)") (class "Default")
      (node (ref "U6") (pin "58") (pinfunction "IO_58") (pintype "bidirectional"))
    )
    (net (code "113") (name "unconnected-(U6A-IO-Pad61)") (class "Default")
      (node (ref "U6") (pin "61") (pinfunction "IO_61") (pintype "bidirectional"))
    )
    (net (code "114") (name "unconnected-(U6A-IO-Pad66)") (class "Default")
      (node (ref "U6") (pin "66") (pinfunction "IO_66") (pintype "bidirectional"))
    )
    (net (code "115") (name "unconnected-(U6A-IO-Pad67)") (class "Default")
      (node (ref "U6") (pin "67") (pinfunction "IO_67") (pintype "bidirectional"))
    )
    (net (code "116") (name "unconnected-(U6A-IO-Pad68)") (class "Default")
      (node (ref "U6") (pin "68") (pinfunction "IO_68") (pintype "bidirectional"))
    )
    (net (code "117") (name "unconnected-(U6A-IO-Pad69)") (class "Default")
      (node (ref "U6") (pin "69") (pinfunction "IO_69") (pintype "bidirectional"))
    )
    (net (code "118") (name "unconnected-(U6A-IO-Pad70)") (class "Default")
      (node (ref "U6") (pin "70") (pinfunction "IO_70") (pintype "bidirectional"))
    )
    (net (code "119") (name "unconnected-(U6A-IO-Pad71)") (class "Default")
      (node (ref "U6") (pin "71") (pinfunction "IO_71") (pintype "bidirectional"))
    )
    (net (code "120") (name "unconnected-(U6A-IO-Pad72)") (class "Default")
      (node (ref "U6") (pin "72") (pinfunction "IO_72") (pintype "bidirectional"))
    )
    (net (code "121") (name "unconnected-(U6A-IO-Pad73)") (class "Default")
      (node (ref "U6") (pin "73") (pinfunction "IO_73") (pintype "bidirectional"))
    )
    (net (code "122") (name "unconnected-(U6A-IO-Pad74)") (class "Default")
      (node (ref "U6") (pin "74") (pinfunction "IO_74") (pintype "bidirectional"))
    )
    (net (code "123") (name "unconnected-(U6A-IO-Pad75)") (class "Default")
      (node (ref "U6") (pin "75") (pinfunction "IO_75") (pintype "bidirectional"))
    )
    (net (code "124") (name "unconnected-(U6A-IO-Pad76)") (class "Default")
      (node (ref "U6") (pin "76") (pinfunction "IO_76") (pintype "bidirectional"))
    )
    (net (code "125") (name "unconnected-(U6A-IO-Pad78)") (class "Default")
      (node (ref "U6") (pin "78") (pinfunction "IO_78") (pintype "bidirectional"))
    )
    (net (code "126") (name "unconnected-(U6A-IO-Pad81)") (class "Default")
      (node (ref "U6") (pin "81") (pinfunction "IO_81") (pintype "bidirectional"))
    )
    (net (code "127") (name "unconnected-(U6A-IO-Pad82)") (class "Default")
      (node (ref "U6") (pin "82") (pinfunction "IO_82") (pintype "bidirectional"))
    )
    (net (code "128") (name "unconnected-(U6A-IO-Pad84)") (class "Default")
      (node (ref "U6") (pin "84") (pinfunction "IO_84") (pintype "bidirectional"))
    )
    (net (code "129") (name "unconnected-(U6A-IO-Pad85)") (class "Default")
      (node (ref "U6") (pin "85") (pinfunction "IO_85") (pintype "bidirectional"))
    )
    (net (code "130") (name "unconnected-(U6A-IO-Pad86)") (class "Default")
      (node (ref "U6") (pin "86") (pinfunction "IO_86") (pintype "bidirectional"))
    )
    (net (code "131") (name "unconnected-(U6A-IO-Pad87)") (class "Default")
      (node (ref "U6") (pin "87") (pinfunction "IO_87") (pintype "bidirectional"))
    )
    (net (code "132") (name "unconnected-(U6A-IO-Pad89)") (class "Default")
      (node (ref "U6") (pin "89") (pinfunction "IO_89") (pintype "bidirectional"))
    )
    (net (code "133") (name "unconnected-(U6A-IO-Pad90)") (class "Default")
      (node (ref "U6") (pin "90") (pinfunction "IO_90") (pintype "bidirectional"))
    )
    (net (code "134") (name "unconnected-(U6A-IO-Pad91)") (class "Default")
      (node (ref "U6") (pin "91") (pinfunction "IO_91") (pintype "bidirectional"))
    )
    (net (code "135") (name "unconnected-(U6A-IO-Pad95)") (class "Default")
      (node (ref "U6") (pin "95") (pinfunction "IO_95") (pintype "bidirectional"))
    )
    (net (code "136") (name "unconnected-(U6A-IO-Pad96)") (class "Default")
      (node (ref "U6") (pin "96") (pinfunction "IO_96") (pintype "bidirectional"))
    )
    (net (code "137") (name "unconnected-(U6A-IO-Pad97)") (class "Default")
      (node (ref "U6") (pin "97") (pinfunction "IO_97") (pintype "bidirectional"))
    )
    (net (code "138") (name "unconnected-(U6A-IO-Pad99)") (class "Default")
      (node (ref "U6") (pin "99") (pinfunction "IO_99") (pintype "bidirectional"))
    )
    (net (code "139") (name "unconnected-(U6A-IO{slash}DEV_OE-Pad43)") (class "Default")
      (node (ref "U6") (pin "43") (pinfunction "IO/DEV_OE_43") (pintype "bidirectional"))
    )
    (net (code "140") (name "unconnected-(U6A-IO{slash}GCLK0-Pad12)") (class "Default")
      (node (ref "U6") (pin "12") (pinfunction "IO/GCLK0_12") (pintype "bidirectional"))
    )
    (net (code "141") (name "unconnected-(U6A-IO{slash}GCLK1-Pad14)") (class "Default")
      (node (ref "U6") (pin "14") (pinfunction "IO/GCLK1_14") (pintype "bidirectional"))
    )
    (net (code "142") (name "unconnected-(U6A-IO{slash}GCLK2-Pad62)") (class "Default")
      (node (ref "U6") (pin "62") (pinfunction "IO/GCLK2_62") (pintype "bidirectional"))
    )
  )
)
